# SoC_pwr_2.net
KiCad netlist of a schematic drawn in Altium Designer
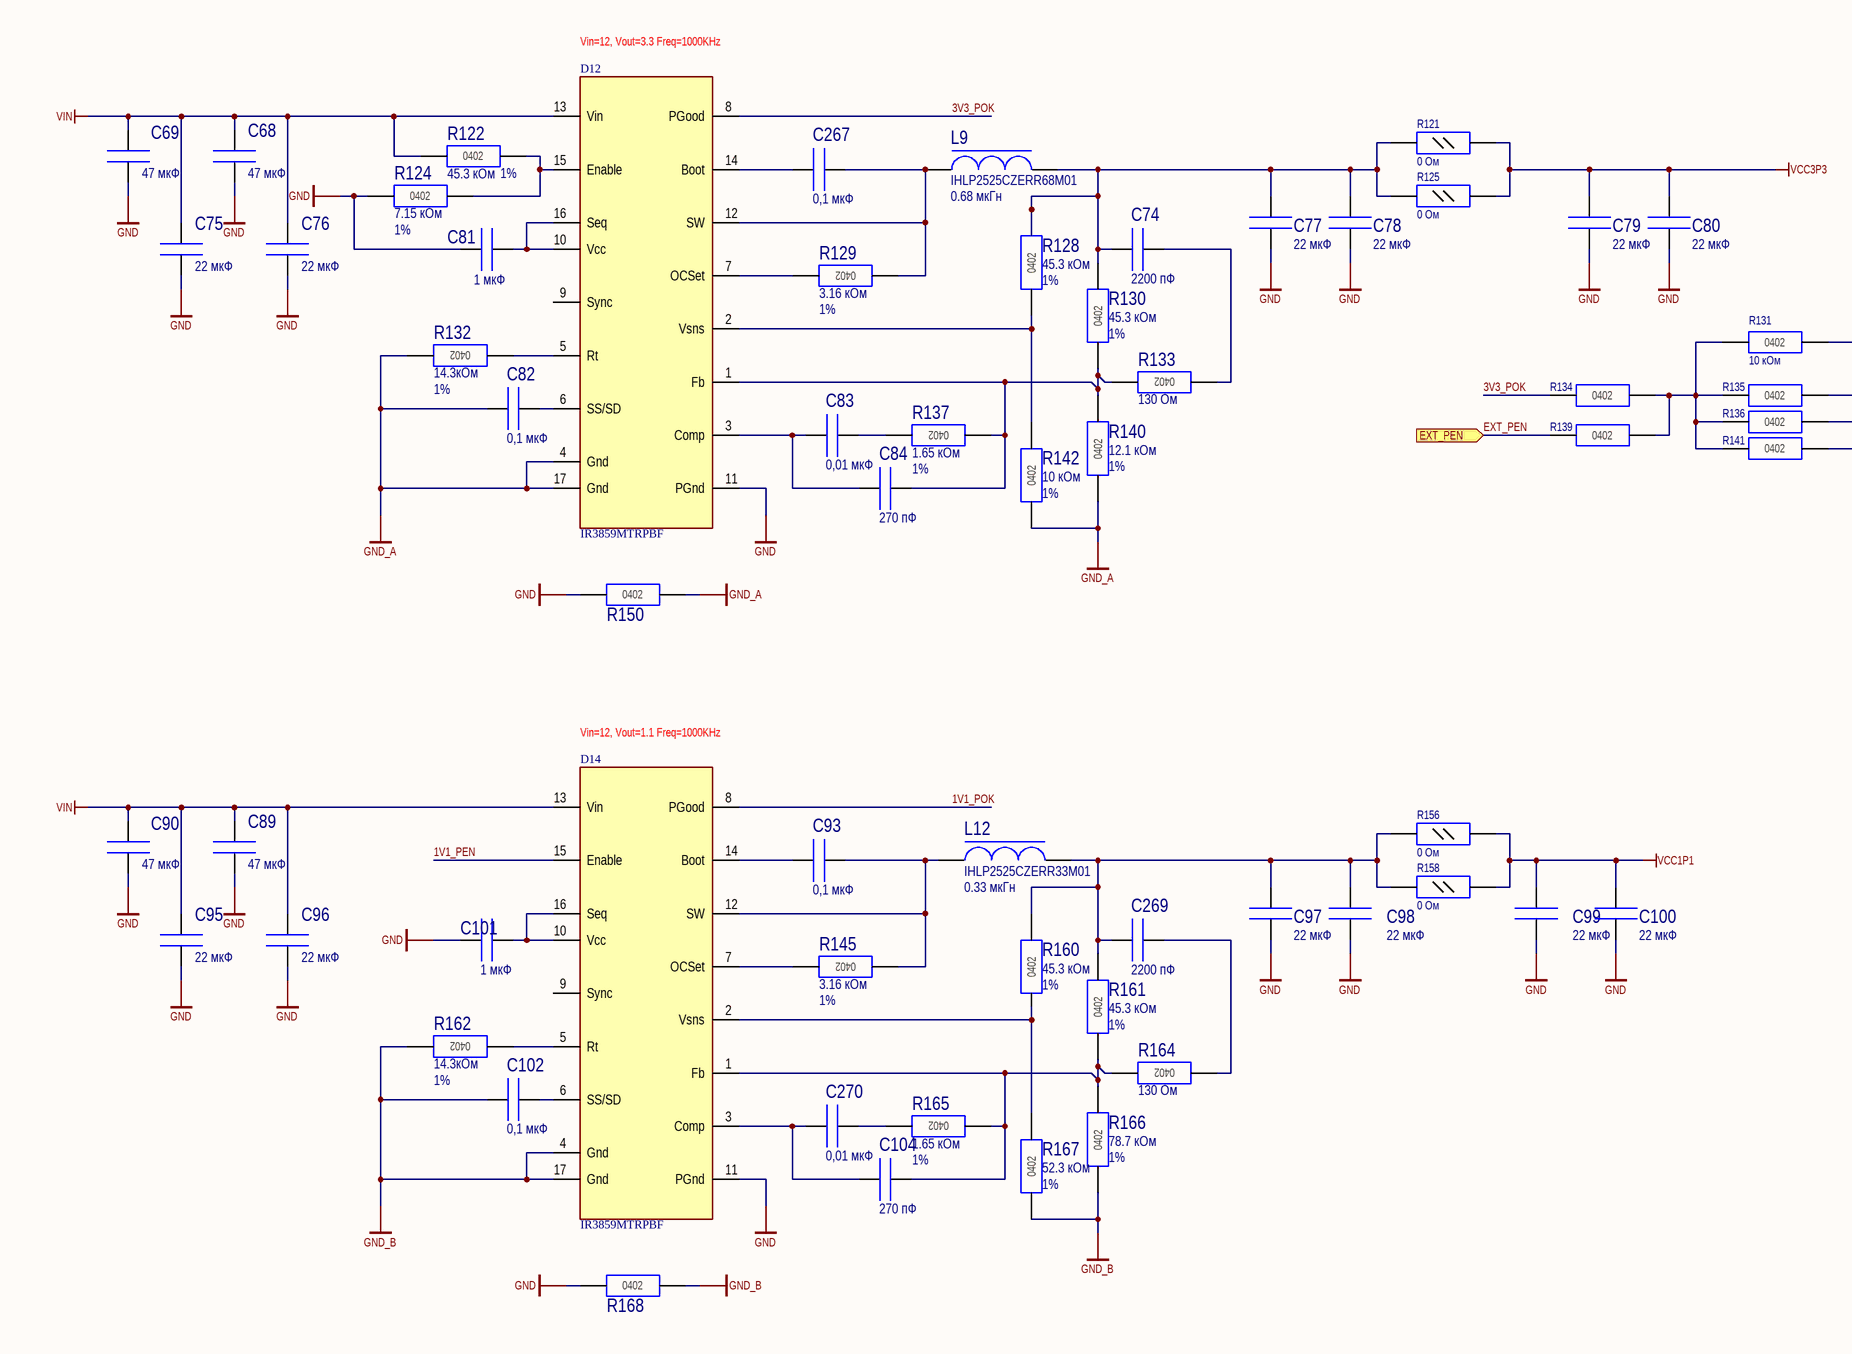
[diagram p0: SoC_pwr_2.SchDoc, left]
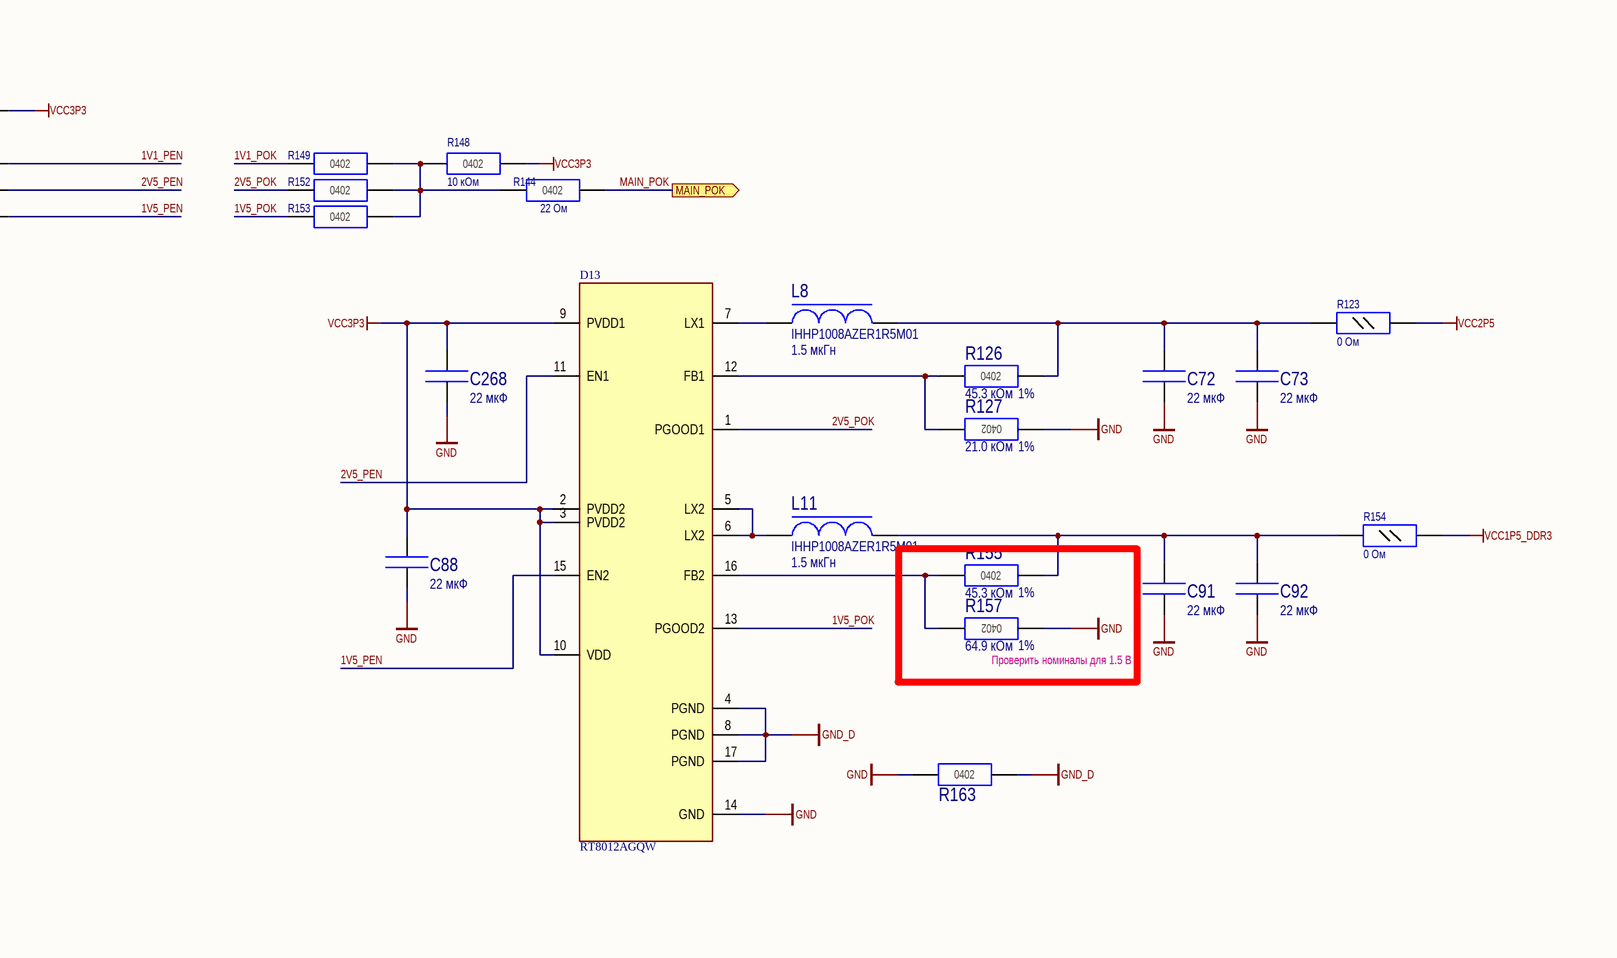
[diagram p1: SoC_pwr_2.SchDoc, right]

(export (version "E")
  (design (tool "Eeschema 10.0.6"))
  (components
    (comp (ref "C68")
      (value "47 мкФ")
      (footprint "CC0603")
      (description "Чип конденсатор керамический")
      (fields (field (name "Comment") "CC0603-X5R-47 мкФ-20%-6,3В"))
      (libsource (lib "Конденсаторы") (part "CC0603-X5R-#-20%-6,3В"))
    )
    (comp (ref "C69")
      (value "47 мкФ")
      (footprint "CC0603")
      (description "Чип конденсатор керамический")
      (fields (field (name "Comment") "CC0603-X5R-47 мкФ-20%-6,3В"))
      (libsource (lib "Конденсаторы") (part "CC0603-X5R-#-20%-6,3В"))
    )
    (comp (ref "C72")
      (value "22 мкФ")
      (footprint "CC0603")
      (description "Чип конденсатор керамический")
      (fields (field (name "Comment") "CC0603-X5R-22 мкФ-20%-6,3В"))
      (libsource (lib "Конденсаторы") (part "CC0603-X5R-#-20%-6,3В"))
    )
    (comp (ref "C73")
      (value "22 мкФ")
      (footprint "CC0603")
      (description "Чип конденсатор керамический")
      (fields (field (name "Comment") "CC0603-X5R-22 мкФ-20%-6,3В"))
      (libsource (lib "Конденсаторы") (part "CC0603-X5R-#-20%-6,3В"))
    )
    (comp (ref "C74")
      (value "2200 пФ")
      (footprint "CC0402(1005)")
      (description "Чип конденсатор керамический")
      (fields (field (name "Comment") "CC0402-X7R-2200 пФ-10%-16В"))
      (libsource (lib "Чип конденсаторы") (part "CC0402-X7R-#-20%-10В"))
    )
    (comp (ref "C75")
      (value "22 мкФ")
      (footprint "CC0603")
      (description "Чип конденсатор керамический")
      (fields (field (name "Comment") "CC0603-X5R-22 мкФ-20%-6,3В"))
      (libsource (lib "Конденсаторы") (part "CC0603-X5R-#-20%-6,3В"))
    )
    (comp (ref "C76")
      (value "22 мкФ")
      (footprint "CC0603")
      (description "Чип конденсатор керамический")
      (fields (field (name "Comment") "CC0603-X5R-22 мкФ-20%-6,3В"))
      (libsource (lib "Конденсаторы") (part "CC0603-X5R-#-20%-6,3В"))
    )
    (comp (ref "C77")
      (value "22 мкФ")
      (footprint "CC0603")
      (description "Чип конденсатор керамический")
      (fields (field (name "Comment") "CC0603-X5R-22 мкФ-20%-6,3В"))
      (libsource (lib "Конденсаторы") (part "CC0603-X5R-#-20%-6,3В"))
    )
    (comp (ref "C78")
      (value "22 мкФ")
      (footprint "CC0603")
      (description "Чип конденсатор керамический")
      (fields (field (name "Comment") "CC0603-X5R-22 мкФ-20%-6,3В"))
      (libsource (lib "Конденсаторы") (part "CC0603-X5R-#-20%-6,3В"))
    )
    (comp (ref "C79")
      (value "22 мкФ")
      (footprint "CC0603")
      (description "Чип конденсатор керамический")
      (fields (field (name "Comment") "CC0603-X5R-22 мкФ-20%-6,3В"))
      (libsource (lib "Конденсаторы") (part "CC0603-X5R-#-20%-6,3В"))
    )
    (comp (ref "C80")
      (value "22 мкФ")
      (footprint "CC0603")
      (description "Чип конденсатор керамический")
      (fields (field (name "Comment") "CC0603-X5R-22 мкФ-20%-6,3В"))
      (libsource (lib "Конденсаторы") (part "CC0603-X5R-#-20%-6,3В"))
    )
    (comp (ref "C81")
      (value "1 мкФ")
      (footprint "CC0603")
      (description "Чип конденсатор керамический")
      (fields (field (name "Comment") "CC0603-X5R-1 мкФ-10%-25В"))
      (libsource (lib "Конденсаторы") (part "CC0603-X5R-#-20%-6,3В"))
    )
    (comp (ref "C82")
      (value "0,1 мкФ")
      (footprint "CC0402(1005)")
      (description "Чип конденсатор керамический")
      (fields (field (name "Comment") "CC0402-X7R-0,1 мкФ-20%-10В"))
      (libsource (lib "Чип конденсаторы") (part "CC0402-X7R-#-20%-10В"))
    )
    (comp (ref "C83")
      (value "0,01 мкФ")
      (footprint "CC0402(1005)")
      (description "Чип конденсатор керамический")
      (fields (field (name "Comment") "CC0402-X7R-0,01 мкФ-10%-50В"))
      (libsource (lib "Чип конденсаторы") (part "CC0402-X7R-#-20%-10В"))
    )
    (comp (ref "C84")
      (value "270 пФ")
      (footprint "CC0402(1005)")
      (description "Чип конденсатор керамический")
      (fields (field (name "Comment") "CC0402-NP0-270 пФ-1%-50В"))
      (libsource (lib "Чип конденсаторы") (part "CC0402-X7R-#-20%-10В"))
    )
    (comp (ref "C88")
      (value "22 мкФ")
      (footprint "CC0603")
      (description "Чип конденсатор керамический")
      (fields (field (name "Comment") "CC0603-X5R-22 мкФ-20%-6,3В"))
      (libsource (lib "Конденсаторы") (part "CC0603-X5R-#-20%-6,3В"))
    )
    (comp (ref "C89")
      (value "47 мкФ")
      (footprint "CC0603")
      (description "Чип конденсатор керамический")
      (fields (field (name "Comment") "CC0603-X5R-47 мкФ-20%-6,3В"))
      (libsource (lib "Конденсаторы") (part "CC0603-X5R-#-20%-6,3В"))
    )
    (comp (ref "C90")
      (value "47 мкФ")
      (footprint "CC0603")
      (description "Чип конденсатор керамический")
      (fields (field (name "Comment") "CC0603-X5R-47 мкФ-20%-6,3В"))
      (libsource (lib "Конденсаторы") (part "CC0603-X5R-#-20%-6,3В"))
    )
    (comp (ref "C91")
      (value "22 мкФ")
      (footprint "CC0603")
      (description "Чип конденсатор керамический")
      (fields (field (name "Comment") "CC0603-X5R-22 мкФ-20%-6,3В"))
      (libsource (lib "Конденсаторы") (part "CC0603-X5R-#-20%-6,3В"))
    )
    (comp (ref "C92")
      (value "22 мкФ")
      (footprint "CC0603")
      (description "Чип конденсатор керамический")
      (fields (field (name "Comment") "CC0603-X5R-22 мкФ-20%-6,3В"))
      (libsource (lib "Конденсаторы") (part "CC0603-X5R-#-20%-6,3В"))
    )
    (comp (ref "C93")
      (value "0,1 мкФ")
      (footprint "CC0402(1005)")
      (description "Чип конденсатор керамический")
      (fields (field (name "Comment") "CC0402-X7R-0,1 мкФ-20%-10В"))
      (libsource (lib "Чип конденсаторы") (part "CC0402-X7R-#-20%-10В"))
    )
    (comp (ref "C95")
      (value "22 мкФ")
      (footprint "CC0603")
      (description "Чип конденсатор керамический")
      (fields (field (name "Comment") "CC0603-X5R-22 мкФ-20%-6,3В"))
      (libsource (lib "Конденсаторы") (part "CC0603-X5R-#-20%-6,3В"))
    )
    (comp (ref "C96")
      (value "22 мкФ")
      (footprint "CC0603")
      (description "Чип конденсатор керамический")
      (fields (field (name "Comment") "CC0603-X5R-22 мкФ-20%-6,3В"))
      (libsource (lib "Конденсаторы") (part "CC0603-X5R-#-20%-6,3В"))
    )
    (comp (ref "C97")
      (value "22 мкФ")
      (footprint "CC0603")
      (description "Чип конденсатор керамический")
      (fields (field (name "Comment") "CC0603-X5R-22 мкФ-20%-6,3В"))
      (libsource (lib "Конденсаторы") (part "CC0603-X5R-#-20%-6,3В"))
    )
    (comp (ref "C98")
      (value "22 мкФ")
      (footprint "CC0603")
      (description "Чип конденсатор керамический")
      (fields (field (name "Comment") "CC0603-X5R-22 мкФ-20%-6,3В"))
      (libsource (lib "Конденсаторы") (part "CC0603-X5R-#-20%-6,3В"))
    )
    (comp (ref "C99")
      (value "22 мкФ")
      (footprint "CC0603")
      (description "Чип конденсатор керамический")
      (fields (field (name "Comment") "CC0603-X5R-22 мкФ-20%-6,3В"))
      (libsource (lib "Конденсаторы") (part "CC0603-X5R-#-20%-6,3В"))
    )
    (comp (ref "C100")
      (value "22 мкФ")
      (footprint "CC0603")
      (description "Чип конденсатор керамический")
      (fields (field (name "Comment") "CC0603-X5R-22 мкФ-20%-6,3В"))
      (libsource (lib "Конденсаторы") (part "CC0603-X5R-#-20%-6,3В"))
    )
    (comp (ref "C101")
      (value "1 мкФ")
      (footprint "CC0603")
      (description "Чип конденсатор керамический")
      (fields (field (name "Comment") "CC0603-X5R-1 мкФ-10%-25В"))
      (libsource (lib "Конденсаторы") (part "CC0603-X5R-#-20%-6,3В"))
    )
    (comp (ref "C102")
      (value "0,1 мкФ")
      (footprint "CC0402(1005)")
      (description "Чип конденсатор керамический")
      (fields (field (name "Comment") "CC0402-X7R-0,1 мкФ-20%-10В"))
      (libsource (lib "Чип конденсаторы") (part "CC0402-X7R-#-20%-10В"))
    )
    (comp (ref "C104")
      (value "270 пФ")
      (footprint "CC0402(1005)")
      (description "Чип конденсатор керамический")
      (fields (field (name "Comment") "CC0402-NP0-270 пФ-1%-50В"))
      (libsource (lib "Чип конденсаторы") (part "CC0402-X7R-#-20%-10В"))
    )
    (comp (ref "C267")
      (value "0,1 мкФ")
      (footprint "CC0402(1005)")
      (description "Чип конденсатор керамический")
      (fields (field (name "Comment") "CC0402-X7R-0,1 мкФ-20%-10В"))
      (libsource (lib "Чип конденсаторы") (part "CC0402-X7R-#-20%-10В"))
    )
    (comp (ref "C268")
      (value "22 мкФ")
      (footprint "CC0603")
      (description "Чип конденсатор керамический")
      (fields (field (name "Comment") "CC0603-X5R-22 мкФ-20%-6,3В"))
      (libsource (lib "Конденсаторы") (part "CC0603-X5R-#-20%-6,3В"))
    )
    (comp (ref "C269")
      (value "2200 пФ")
      (footprint "CC0402(1005)")
      (description "Чип конденсатор керамический")
      (fields (field (name "Comment") "CC0402-X7R-2200 пФ-10%-16В"))
      (libsource (lib "Чип конденсаторы") (part "CC0402-X7R-#-20%-10В"))
    )
    (comp (ref "C270")
      (value "0,01 мкФ")
      (footprint "CC0402(1005)")
      (description "Чип конденсатор керамический")
      (fields (field (name "Comment") "CC0402-X7R-0,01 мкФ-10%-50В"))
      (libsource (lib "Чип конденсаторы") (part "CC0402-X7R-#-20%-10В"))
    )
    (comp (ref "D12")
      (value "IR3859MTRPBF")
      (footprint "IR3859")
      (description "IC REG BUCK ADJ 9A SYNC 17PQFN")
      (libsource (lib "SD_IC") (part "IR3859MPbF"))
    )
    (comp (ref "D13")
      (value "RT8012AGQW")
      (footprint "RT8012AGQW")
      (libsource (lib "SD_IC") (part "RT8012AGQW"))
    )
    (comp (ref "D14")
      (value "IR3859MTRPBF")
      (footprint "IR3859")
      (description "IC REG BUCK ADJ 9A SYNC 17PQFN")
      (libsource (lib "SD_IC") (part "IR3859MPbF"))
    )
    (comp (ref "L8")
      (value "IHHP1008AZER1R5M01")
      (footprint "INDC2720X12L")
      (description "FIXED IND 1.5UH 2.4A 96 MOHM SMD")
      (fields (field (name "ALTIUM_VALUE") "1.5 мкГн"))
      (libsource (lib "SD_IC") (part "L_VISH_IIHHP1008ABE_1"))
    )
    (comp (ref "L9")
      (value "IHLP2525CZERR68M01")
      (footprint "INDP6965X30L")
      (description "FIXED IND 680NH 15.5A 5.5 MOHM")
      (fields (field (name "ALTIUM_VALUE") "0.68 мкГн"))
      (libsource (lib "SD_IC") (part "L_VISH_IHLP2525CZERR68M01"))
    )
    (comp (ref "L11")
      (value "IHHP1008AZER1R5M01")
      (footprint "INDC2720X12L")
      (description "FIXED IND 1.5UH 2.4A 96 MOHM SMD")
      (fields (field (name "ALTIUM_VALUE") "1.5 мкГн"))
      (libsource (lib "SD_IC") (part "L_VISH_IIHHP1008ABE_1"))
    )
    (comp (ref "L12")
      (value "IHLP2525CZERR33M01")
      (footprint "INDP6965X30L")
      (description "FIXED IND 680NH 15.5A 5.5 MOHM")
      (fields (field (name "ALTIUM_VALUE") "0.33 мкГн"))
      (libsource (lib "SD_IC") (part "L_VISH_IHLP2525CZERR68M01"))
    )
    (comp (ref "R121")
      (value "0 Ом")
      (footprint "CR0805")
      (description "Чип резистор")
      (fields (field (name "Comment") "CR0805-0 Ом-±5%"))
      (libsource (lib "Резисторы") (part "CR0805-#-±5%"))
    )
    (comp (ref "R122")
      (value "45.3 кОм")
      (footprint "CR0402(1005)")
      (description "Чип резистор")
      (fields (field (name "TOLERANCE") "1%") (field (name "Comment") "CR0402-45.3 кОм-±1%"))
      (libsource (lib "") (part "CR0402-#-±1%_2"))
    )
    (comp (ref "R123")
      (value "0 Ом")
      (footprint "CR0805")
      (description "Чип резистор")
      (fields (field (name "Comment") "CR0805-0 Ом-±5%"))
      (libsource (lib "Резисторы") (part "CR0805-#-±5%"))
    )
    (comp (ref "R124")
      (value "7.15 кОм")
      (footprint "CR0402(1005)")
      (description "Чип резистор")
      (fields (field (name "TOLERANCE") "1%") (field (name "Comment") "CR0402-7.15 кОм-±1%"))
      (libsource (lib "") (part "CR0402-#-±1%_2"))
    )
    (comp (ref "R125")
      (value "0 Ом")
      (footprint "CR0805")
      (description "Чип резистор")
      (fields (field (name "Comment") "CR0805-0 Ом-±5%"))
      (libsource (lib "Резисторы") (part "CR0805-#-±5%"))
    )
    (comp (ref "R126")
      (value "45.3 кОм")
      (footprint "CR0402(1005)")
      (description "Чип резистор")
      (fields (field (name "TOLERANCE") "1%") (field (name "Comment") "CR0402-45.3 кОм-±1%"))
      (libsource (lib "") (part "CR0402-#-±1%_2"))
    )
    (comp (ref "R127")
      (value "21.0 кОм")
      (footprint "CR0402(1005)")
      (description "Чип резистор")
      (fields (field (name "TOLERANCE") "1%") (field (name "Comment") "CR0402-21.0 кОм-±1%"))
      (libsource (lib "") (part "CR0402-#-±1%_1"))
    )
    (comp (ref "R128")
      (value "45.3 кОм")
      (footprint "CR0402(1005)")
      (description "Чип резистор")
      (fields (field (name "TOLERANCE") "1%") (field (name "Comment") "CR0402-45.3 кОм-±1%"))
      (libsource (lib "Чип резисторы") (part "CR0402-#-±1%"))
    )
    (comp (ref "R129")
      (value "3.16 кОм")
      (footprint "CR0402(1005)")
      (description "Чип резистор")
      (fields (field (name "TOLERANCE") "1%") (field (name "Comment") "CR0402-3.16 кОм-±1%"))
      (libsource (lib "") (part "CR0402-#-±1%_1"))
    )
    (comp (ref "R130")
      (value "45.3 кОм")
      (footprint "CR0402(1005)")
      (description "Чип резистор")
      (fields (field (name "TOLERANCE") "1%") (field (name "Comment") "CR0402-45.3 кОм-±1%"))
      (libsource (lib "Чип резисторы") (part "CR0402-#-±1%"))
    )
    (comp (ref "R131")
      (value "10 кОм")
      (footprint "CR0402(1005)")
      (description "Чип резистор")
      (fields (field (name "TOLERANCE") "5%") (field (name "Comment") "CR0402-10 кОм-±5%"))
      (libsource (lib "Резисторы") (part "CR0402-#-±5%"))
    )
    (comp (ref "R132")
      (value "14.3кОм")
      (footprint "CR0402(1005)")
      (description "Чип резистор")
      (fields (field (name "TOLERANCE") "1%") (field (name "Comment") "CR0402-14.3кОм-±1%"))
      (libsource (lib "") (part "CR0402-#-±1%_1"))
    )
    (comp (ref "R133")
      (value "130 Ом")
      (footprint "CR0402(1005)")
      (description "Чип резистор")
      (fields (field (name "Comment") "CR0402-130 Ом-±1%"))
      (libsource (lib "") (part "CR0402-#-±1%_1"))
    )
    (comp (ref "R134")
      (value "CR0402-0 Ом-±5%")
      (footprint "CR0402(1005)")
      (description "Чип резистор")
      (fields (field (name "TOLERANCE") "5%"))
      (libsource (lib "Резисторы") (part "CR0402-#-±5%"))
    )
    (comp (ref "R135")
      (value "CR0402-0 Ом-±5%")
      (footprint "CR0402(1005)")
      (description "Чип резистор")
      (fields (field (name "TOLERANCE") "5%"))
      (libsource (lib "Резисторы") (part "CR0402-#-±5%"))
    )
    (comp (ref "R136")
      (value "CR0402-0 Ом-±5%")
      (footprint "CR0402(1005)")
      (description "Чип резистор")
      (fields (field (name "TOLERANCE") "5%"))
      (libsource (lib "Резисторы") (part "CR0402-#-±5%"))
    )
    (comp (ref "R137")
      (value "1.65 кОм")
      (footprint "CR0402(1005)")
      (description "Чип резистор")
      (fields (field (name "TOLERANCE") "1%") (field (name "Comment") "CR0402-1.65 кОм-±1%"))
      (libsource (lib "") (part "CR0402-#-±1%_1"))
    )
    (comp (ref "R139")
      (value "CR0402-0 Ом-±5%")
      (footprint "CR0402(1005)")
      (description "Чип резистор")
      (fields (field (name "TOLERANCE") "5%"))
      (libsource (lib "Резисторы") (part "CR0402-#-±5%"))
    )
    (comp (ref "R140")
      (value "12.1 кОм")
      (footprint "CR0402(1005)")
      (description "Чип резистор")
      (fields (field (name "TOLERANCE") "1%") (field (name "Comment") "CR0402-12.1 кОм-±1%"))
      (libsource (lib "Чип резисторы") (part "CR0402-#-±1%"))
    )
    (comp (ref "R141")
      (value "CR0402-0 Ом-±5%")
      (footprint "CR0402(1005)")
      (description "Чип резистор")
      (fields (field (name "TOLERANCE") "5%"))
      (libsource (lib "Резисторы") (part "CR0402-#-±5%"))
    )
    (comp (ref "R142")
      (value "10 кОм")
      (footprint "CR0402(1005)")
      (description "Чип резистор")
      (fields (field (name "TOLERANCE") "1%") (field (name "Comment") "CR0402-10 кОм-±1%"))
      (libsource (lib "Чип резисторы") (part "CR0402-#-±1%"))
    )
    (comp (ref "R144")
      (value "22 Ом")
      (footprint "CR0402(1005)")
      (description "Чип резистор")
      (fields (field (name "TOLERANCE") "5%") (field (name "Comment") "CR0402-22 Ом-±5%"))
      (libsource (lib "Чип резисторы") (part "CR0402-#-±5%"))
    )
    (comp (ref "R145")
      (value "3.16 кОм")
      (footprint "CR0402(1005)")
      (description "Чип резистор")
      (fields (field (name "TOLERANCE") "1%") (field (name "Comment") "CR0402-3.16 кОм-±1%"))
      (libsource (lib "") (part "CR0402-#-±1%_1"))
    )
    (comp (ref "R148")
      (value "10 кОм")
      (footprint "CR0402(1005)")
      (description "Чип резистор")
      (fields (field (name "TOLERANCE") "5%") (field (name "Comment") "CR0402-10 кОм-±5%"))
      (libsource (lib "Резисторы") (part "CR0402-#-±5%"))
    )
    (comp (ref "R149")
      (value "CR0402-0 Ом-±5%")
      (footprint "CR0402(1005)")
      (description "Чип резистор")
      (fields (field (name "TOLERANCE") "5%"))
      (libsource (lib "Резисторы") (part "CR0402-#-±5%"))
    )
    (comp (ref "R150")
      (value "CR0402-0 Ом-±5%")
      (footprint "CR0402(1005)")
      (description "Чип резистор")
      (fields (field (name "TOLERANCE") "5%"))
      (libsource (lib "Резисторы") (part "CR0402-#-±5%"))
    )
    (comp (ref "R152")
      (value "CR0402-0 Ом-±5%")
      (footprint "CR0402(1005)")
      (description "Чип резистор")
      (fields (field (name "TOLERANCE") "5%"))
      (libsource (lib "Резисторы") (part "CR0402-#-±5%"))
    )
    (comp (ref "R153")
      (value "CR0402-0 Ом-±5%")
      (footprint "CR0402(1005)")
      (description "Чип резистор")
      (fields (field (name "TOLERANCE") "5%"))
      (libsource (lib "Резисторы") (part "CR0402-#-±5%"))
    )
    (comp (ref "R154")
      (value "0 Ом")
      (footprint "CR0805")
      (description "Чип резистор")
      (fields (field (name "Comment") "CR0805-0 Ом-±5%"))
      (libsource (lib "Резисторы") (part "CR0805-#-±5%"))
    )
    (comp (ref "R155")
      (value "45.3 кОм")
      (footprint "CR0402(1005)")
      (description "Чип резистор")
      (fields (field (name "TOLERANCE") "1%") (field (name "Comment") "CR0402-45.3 кОм-±1%"))
      (libsource (lib "") (part "CR0402-#-±1%_2"))
    )
    (comp (ref "R156")
      (value "0 Ом")
      (footprint "CR0805")
      (description "Чип резистор")
      (fields (field (name "Comment") "CR0805-0 Ом-±5%"))
      (libsource (lib "Резисторы") (part "CR0805-#-±5%"))
    )
    (comp (ref "R157")
      (value "64.9 кОм")
      (footprint "CR0402(1005)")
      (description "Чип резистор")
      (fields (field (name "TOLERANCE") "1%") (field (name "Comment") "CR0402-64.9 кОм-±1%"))
      (libsource (lib "") (part "CR0402-#-±1%_1"))
    )
    (comp (ref "R158")
      (value "0 Ом")
      (footprint "CR0805")
      (description "Чип резистор")
      (fields (field (name "Comment") "CR0805-0 Ом-±5%"))
      (libsource (lib "Резисторы") (part "CR0805-#-±5%"))
    )
    (comp (ref "R160")
      (value "45.3 кОм")
      (footprint "CR0402(1005)")
      (description "Чип резистор")
      (fields (field (name "TOLERANCE") "1%") (field (name "Comment") "CR0402-45.3 кОм-±1%"))
      (libsource (lib "Чип резисторы") (part "CR0402-#-±1%"))
    )
    (comp (ref "R161")
      (value "45.3 кОм")
      (footprint "CR0402(1005)")
      (description "Чип резистор")
      (fields (field (name "TOLERANCE") "1%") (field (name "Comment") "CR0402-45.3 кОм-±1%"))
      (libsource (lib "Чип резисторы") (part "CR0402-#-±1%"))
    )
    (comp (ref "R162")
      (value "14.3кОм")
      (footprint "CR0402(1005)")
      (description "Чип резистор")
      (fields (field (name "TOLERANCE") "1%") (field (name "Comment") "CR0402-14.3кОм-±1%"))
      (libsource (lib "") (part "CR0402-#-±1%_1"))
    )
    (comp (ref "R163")
      (value "CR0402-0 Ом-±5%")
      (footprint "CR0402(1005)")
      (description "Чип резистор")
      (fields (field (name "TOLERANCE") "5%"))
      (libsource (lib "Резисторы") (part "CR0402-#-±5%"))
    )
    (comp (ref "R164")
      (value "130 Ом")
      (footprint "CR0402(1005)")
      (description "Чип резистор")
      (fields (field (name "Comment") "CR0402-130 Ом-±1%"))
      (libsource (lib "") (part "CR0402-#-±1%_1"))
    )
    (comp (ref "R165")
      (value "1.65 кОм")
      (footprint "CR0402(1005)")
      (description "Чип резистор")
      (fields (field (name "TOLERANCE") "1%") (field (name "Comment") "CR0402-1.65 кОм-±1%"))
      (libsource (lib "") (part "CR0402-#-±1%_1"))
    )
    (comp (ref "R166")
      (value "78.7 кОм")
      (footprint "CR0402(1005)")
      (description "Чип резистор")
      (fields (field (name "TOLERANCE") "1%") (field (name "Comment") "CR0402-78.7 кОм-±1%"))
      (libsource (lib "Чип резисторы") (part "CR0402-#-±1%"))
    )
    (comp (ref "R167")
      (value "52.3 кОм")
      (footprint "CR0402(1005)")
      (description "Чип резистор")
      (fields (field (name "TOLERANCE") "1%") (field (name "Comment") "CR0402-52.3 кОм-±1%"))
      (libsource (lib "Чип резисторы") (part "CR0402-#-±1%"))
    )
    (comp (ref "R168")
      (value "CR0402-0 Ом-±5%")
      (footprint "CR0402(1005)")
      (description "Чип резистор")
      (fields (field (name "TOLERANCE") "5%"))
      (libsource (lib "Резисторы") (part "CR0402-#-±5%"))
    )
  )
  (nets
    (net (code "1") (name "/1V1_PEN") (class "Default")
      (node (ref "D14") (pin "15") (pinfunction "Enable_15") (pintype "passive"))
      (node (ref "R135") (pin "2") (pinfunction "-_2") (pintype "passive"))
    )
    (net (code "2") (name "/1V1_POK") (class "Default")
      (node (ref "D14") (pin "8") (pinfunction "PGood_8") (pintype "passive"))
      (node (ref "R149") (pin "1") (pinfunction "+_1") (pintype "passive"))
    )
    (net (code "3") (name "/1V5_PEN") (class "Default")
      (node (ref "D13") (pin "15") (pinfunction "EN2_15") (pintype "passive"))
      (node (ref "R141") (pin "2") (pinfunction "-_2") (pintype "passive"))
    )
    (net (code "4") (name "/1V5_POK") (class "Default")
      (node (ref "D13") (pin "13") (pinfunction "PGOOD2_13") (pintype "passive"))
      (node (ref "R153") (pin "1") (pinfunction "+_1") (pintype "passive"))
    )
    (net (code "5") (name "/2V5_PEN") (class "Default")
      (node (ref "D13") (pin "11") (pinfunction "EN1_11") (pintype "passive"))
      (node (ref "R136") (pin "2") (pinfunction "-_2") (pintype "passive"))
    )
    (net (code "6") (name "/2V5_POK") (class "Default")
      (node (ref "D13") (pin "1") (pinfunction "PGOOD1_1") (pintype "passive"))
      (node (ref "R152") (pin "1") (pinfunction "+_1") (pintype "passive"))
    )
    (net (code "7") (name "/3V3_POK") (class "Default")
      (node (ref "D12") (pin "8") (pinfunction "PGood_8") (pintype "passive"))
      (node (ref "R134") (pin "1") (pinfunction "+_1") (pintype "passive"))
    )
    (net (code "8") (name "/EXT_PEN") (class "Default")
      (node (ref "R139") (pin "1") (pinfunction "+_1") (pintype "passive"))
    )
    (net (code "9") (name "/MAIN_POK") (class "Default")
      (node (ref "R144") (pin "2") (pinfunction "-_2") (pintype "passive"))
    )
    (net (code "10") (name "GND") (class "Default")
      (node (ref "C100") (pin "2") (pinfunction "-_2") (pintype "passive"))
      (node (ref "C101") (pin "1") (pinfunction "+_1") (pintype "passive"))
      (node (ref "C268") (pin "2") (pinfunction "-_2") (pintype "passive"))
      (node (ref "C68") (pin "2") (pinfunction "-_2") (pintype "passive"))
      (node (ref "C69") (pin "2") (pinfunction "-_2") (pintype "passive"))
      (node (ref "C72") (pin "2") (pinfunction "-_2") (pintype "passive"))
      (node (ref "C73") (pin "2") (pinfunction "-_2") (pintype "passive"))
      (node (ref "C75") (pin "2") (pinfunction "-_2") (pintype "passive"))
      (node (ref "C76") (pin "2") (pinfunction "-_2") (pintype "passive"))
      (node (ref "C77") (pin "2") (pinfunction "-_2") (pintype "passive"))
      (node (ref "C78") (pin "2") (pinfunction "-_2") (pintype "passive"))
      (node (ref "C79") (pin "2") (pinfunction "-_2") (pintype "passive"))
      (node (ref "C80") (pin "2") (pinfunction "-_2") (pintype "passive"))
      (node (ref "C81") (pin "1") (pinfunction "+_1") (pintype "passive"))
      (node (ref "C88") (pin "2") (pinfunction "-_2") (pintype "passive"))
      (node (ref "C89") (pin "2") (pinfunction "-_2") (pintype "passive"))
      (node (ref "C90") (pin "2") (pinfunction "-_2") (pintype "passive"))
      (node (ref "C91") (pin "2") (pinfunction "-_2") (pintype "passive"))
      (node (ref "C92") (pin "2") (pinfunction "-_2") (pintype "passive"))
      (node (ref "C95") (pin "2") (pinfunction "-_2") (pintype "passive"))
      (node (ref "C96") (pin "2") (pinfunction "-_2") (pintype "passive"))
      (node (ref "C97") (pin "2") (pinfunction "-_2") (pintype "passive"))
      (node (ref "C98") (pin "2") (pinfunction "-_2") (pintype "passive"))
      (node (ref "C99") (pin "2") (pinfunction "-_2") (pintype "passive"))
      (node (ref "D12") (pin "11") (pinfunction "PGnd_11") (pintype "passive"))
      (node (ref "D13") (pin "14") (pinfunction "GND_14") (pintype "passive"))
      (node (ref "D14") (pin "11") (pinfunction "PGnd_11") (pintype "passive"))
      (node (ref "R124") (pin "1") (pinfunction "+_1") (pintype "passive"))
      (node (ref "R127") (pin "1") (pinfunction "+_1") (pintype "passive"))
      (node (ref "R150") (pin "1") (pinfunction "+_1") (pintype "passive"))
      (node (ref "R157") (pin "1") (pinfunction "+_1") (pintype "passive"))
      (node (ref "R163") (pin "1") (pinfunction "+_1") (pintype "passive"))
      (node (ref "R168") (pin "1") (pinfunction "+_1") (pintype "passive"))
    )
    (net (code "11") (name "GND_A") (class "Default")
      (node (ref "C82") (pin "1") (pinfunction "+_1") (pintype "passive"))
      (node (ref "D12") (pin "17") (pinfunction "Gnd_17") (pintype "passive"))
      (node (ref "D12") (pin "4") (pinfunction "Gnd_4") (pintype "passive"))
      (node (ref "R132") (pin "2") (pinfunction "-_2") (pintype "passive"))
      (node (ref "R140") (pin "1") (pinfunction "+_1") (pintype "passive"))
      (node (ref "R142") (pin "1") (pinfunction "+_1") (pintype "passive"))
      (node (ref "R150") (pin "2") (pinfunction "-_2") (pintype "passive"))
    )
    (net (code "12") (name "GND_B") (class "Default")
      (node (ref "C102") (pin "1") (pinfunction "+_1") (pintype "passive"))
      (node (ref "D14") (pin "17") (pinfunction "Gnd_17") (pintype "passive"))
      (node (ref "D14") (pin "4") (pinfunction "Gnd_4") (pintype "passive"))
      (node (ref "R162") (pin "2") (pinfunction "-_2") (pintype "passive"))
      (node (ref "R166") (pin "1") (pinfunction "+_1") (pintype "passive"))
      (node (ref "R167") (pin "1") (pinfunction "+_1") (pintype "passive"))
      (node (ref "R168") (pin "2") (pinfunction "-_2") (pintype "passive"))
    )
    (net (code "13") (name "GND_D") (class "Default")
      (node (ref "D13") (pin "17") (pinfunction "PGND_17") (pintype "passive"))
      (node (ref "D13") (pin "4") (pinfunction "PGND_4") (pintype "passive"))
      (node (ref "D13") (pin "8") (pinfunction "PGND_8") (pintype "passive"))
      (node (ref "R163") (pin "2") (pinfunction "-_2") (pintype "passive"))
    )
    (net (code "14") (name "Net-(C72-+)") (class "Default")
      (node (ref "C72") (pin "1") (pinfunction "+_1") (pintype "passive"))
      (node (ref "C73") (pin "1") (pinfunction "+_1") (pintype "passive"))
      (node (ref "L8") (pin "2") (pinfunction "2_2") (pintype "passive"))
      (node (ref "R123") (pin "1") (pinfunction "+_1") (pintype "passive"))
      (node (ref "R126") (pin "2") (pinfunction "-_2") (pintype "passive"))
    )
    (net (code "15") (name "Net-(C74-+)") (class "Default")
      (node (ref "C74") (pin "1") (pinfunction "+_1") (pintype "passive"))
      (node (ref "R133") (pin "1") (pinfunction "+_1") (pintype "passive"))
    )
    (net (code "16") (name "Net-(C74--)") (class "Default")
      (node (ref "C74") (pin "2") (pinfunction "-_2") (pintype "passive"))
      (node (ref "C77") (pin "1") (pinfunction "+_1") (pintype "passive"))
      (node (ref "C78") (pin "1") (pinfunction "+_1") (pintype "passive"))
      (node (ref "L9") (pin "2") (pinfunction "2_2") (pintype "passive"))
      (node (ref "R121") (pin "1") (pinfunction "+_1") (pintype "passive"))
      (node (ref "R125") (pin "1") (pinfunction "+_1") (pintype "passive"))
      (node (ref "R128") (pin "2") (pinfunction "-_2") (pintype "passive"))
      (node (ref "R130") (pin "2") (pinfunction "-_2") (pintype "passive"))
    )
    (net (code "17") (name "Net-(C81--)") (class "Default")
      (node (ref "C81") (pin "2") (pinfunction "-_2") (pintype "passive"))
      (node (ref "D12") (pin "10") (pinfunction "Vcc_10") (pintype "passive"))
      (node (ref "D12") (pin "16") (pinfunction "Seq_16") (pintype "passive"))
    )
    (net (code "18") (name "Net-(C82--)") (class "Default")
      (node (ref "C82") (pin "2") (pinfunction "-_2") (pintype "passive"))
      (node (ref "D12") (pin "6") (pinfunction "SS/SD_6") (pintype "passive"))
    )
    (net (code "19") (name "Net-(C83-+)") (class "Default")
      (node (ref "C83") (pin "1") (pinfunction "+_1") (pintype "passive"))
      (node (ref "C84") (pin "2") (pinfunction "-_2") (pintype "passive"))
      (node (ref "D12") (pin "3") (pinfunction "Comp_3") (pintype "passive"))
    )
    (net (code "20") (name "Net-(C83--)") (class "Default")
      (node (ref "C83") (pin "2") (pinfunction "-_2") (pintype "passive"))
      (node (ref "R137") (pin "2") (pinfunction "-_2") (pintype "passive"))
    )
    (net (code "21") (name "Net-(C84-+)") (class "Default")
      (node (ref "C84") (pin "1") (pinfunction "+_1") (pintype "passive"))
      (node (ref "D12") (pin "1") (pinfunction "Fb_1") (pintype "passive"))
      (node (ref "R130") (pin "1") (pinfunction "+_1") (pintype "passive"))
      (node (ref "R133") (pin "2") (pinfunction "-_2") (pintype "passive"))
      (node (ref "R137") (pin "1") (pinfunction "+_1") (pintype "passive"))
      (node (ref "R140") (pin "2") (pinfunction "-_2") (pintype "passive"))
    )
    (net (code "22") (name "Net-(C91-+)") (class "Default")
      (node (ref "C91") (pin "1") (pinfunction "+_1") (pintype "passive"))
      (node (ref "C92") (pin "1") (pinfunction "+_1") (pintype "passive"))
      (node (ref "L11") (pin "2") (pinfunction "2_2") (pintype "passive"))
      (node (ref "R154") (pin "1") (pinfunction "+_1") (pintype "passive"))
      (node (ref "R155") (pin "2") (pinfunction "-_2") (pintype "passive"))
    )
    (net (code "23") (name "Net-(C93-+)") (class "Default")
      (node (ref "C93") (pin "1") (pinfunction "+_1") (pintype "passive"))
      (node (ref "D14") (pin "14") (pinfunction "Boot_14") (pintype "passive"))
    )
    (net (code "24") (name "Net-(C93--)") (class "Default")
      (node (ref "C93") (pin "2") (pinfunction "-_2") (pintype "passive"))
      (node (ref "D14") (pin "12") (pinfunction "SW_12") (pintype "passive"))
      (node (ref "L12") (pin "1") (pinfunction "1_1") (pintype "passive"))
      (node (ref "R145") (pin "1") (pinfunction "+_1") (pintype "passive"))
    )
    (net (code "25") (name "Net-(C101--)") (class "Default")
      (node (ref "C101") (pin "2") (pinfunction "-_2") (pintype "passive"))
      (node (ref "D14") (pin "10") (pinfunction "Vcc_10") (pintype "passive"))
      (node (ref "D14") (pin "16") (pinfunction "Seq_16") (pintype "passive"))
    )
    (net (code "26") (name "Net-(C102--)") (class "Default")
      (node (ref "C102") (pin "2") (pinfunction "-_2") (pintype "passive"))
      (node (ref "D14") (pin "6") (pinfunction "SS/SD_6") (pintype "passive"))
    )
    (net (code "27") (name "Net-(C104-+)") (class "Default")
      (node (ref "C104") (pin "1") (pinfunction "+_1") (pintype "passive"))
      (node (ref "D14") (pin "1") (pinfunction "Fb_1") (pintype "passive"))
      (node (ref "R161") (pin "1") (pinfunction "+_1") (pintype "passive"))
      (node (ref "R164") (pin "2") (pinfunction "-_2") (pintype "passive"))
      (node (ref "R165") (pin "1") (pinfunction "+_1") (pintype "passive"))
      (node (ref "R166") (pin "2") (pinfunction "-_2") (pintype "passive"))
    )
    (net (code "28") (name "Net-(C104--)") (class "Default")
      (node (ref "C104") (pin "2") (pinfunction "-_2") (pintype "passive"))
      (node (ref "C270") (pin "1") (pinfunction "+_1") (pintype "passive"))
      (node (ref "D14") (pin "3") (pinfunction "Comp_3") (pintype "passive"))
    )
    (net (code "29") (name "Net-(C267-+)") (class "Default")
      (node (ref "C267") (pin "1") (pinfunction "+_1") (pintype "passive"))
      (node (ref "D12") (pin "14") (pinfunction "Boot_14") (pintype "passive"))
    )
    (net (code "30") (name "Net-(C267--)") (class "Default")
      (node (ref "C267") (pin "2") (pinfunction "-_2") (pintype "passive"))
      (node (ref "D12") (pin "12") (pinfunction "SW_12") (pintype "passive"))
      (node (ref "L9") (pin "1") (pinfunction "1_1") (pintype "passive"))
      (node (ref "R129") (pin "1") (pinfunction "+_1") (pintype "passive"))
    )
    (net (code "31") (name "Net-(C269-+)") (class "Default")
      (node (ref "C269") (pin "1") (pinfunction "+_1") (pintype "passive"))
      (node (ref "R164") (pin "1") (pinfunction "+_1") (pintype "passive"))
    )
    (net (code "32") (name "Net-(C269--)") (class "Default")
      (node (ref "C269") (pin "2") (pinfunction "-_2") (pintype "passive"))
      (node (ref "C97") (pin "1") (pinfunction "+_1") (pintype "passive"))
      (node (ref "C98") (pin "1") (pinfunction "+_1") (pintype "passive"))
      (node (ref "L12") (pin "2") (pinfunction "2_2") (pintype "passive"))
      (node (ref "R156") (pin "1") (pinfunction "+_1") (pintype "passive"))
      (node (ref "R158") (pin "1") (pinfunction "+_1") (pintype "passive"))
      (node (ref "R160") (pin "2") (pinfunction "-_2") (pintype "passive"))
      (node (ref "R161") (pin "2") (pinfunction "-_2") (pintype "passive"))
    )
    (net (code "33") (name "Net-(C270--)") (class "Default")
      (node (ref "C270") (pin "2") (pinfunction "-_2") (pintype "passive"))
      (node (ref "R165") (pin "2") (pinfunction "-_2") (pintype "passive"))
    )
    (net (code "34") (name "Net-(D12-Enable)") (class "Default")
      (node (ref "D12") (pin "15") (pinfunction "Enable_15") (pintype "passive"))
      (node (ref "R122") (pin "2") (pinfunction "-_2") (pintype "passive"))
      (node (ref "R124") (pin "2") (pinfunction "-_2") (pintype "passive"))
    )
    (net (code "35") (name "Net-(D12-OCSet)") (class "Default")
      (node (ref "D12") (pin "7") (pinfunction "OCSet_7") (pintype "passive"))
      (node (ref "R129") (pin "2") (pinfunction "-_2") (pintype "passive"))
    )
    (net (code "36") (name "Net-(D12-Rt)") (class "Default")
      (node (ref "D12") (pin "5") (pinfunction "Rt_5") (pintype "passive"))
      (node (ref "R132") (pin "1") (pinfunction "+_1") (pintype "passive"))
    )
    (net (code "37") (name "Net-(D12-Vsns)") (class "Default")
      (node (ref "D12") (pin "2") (pinfunction "Vsns_2") (pintype "passive"))
      (node (ref "R128") (pin "1") (pinfunction "+_1") (pintype "passive"))
      (node (ref "R142") (pin "2") (pinfunction "-_2") (pintype "passive"))
    )
    (net (code "38") (name "Net-(D13-FB1)") (class "Default")
      (node (ref "D13") (pin "12") (pinfunction "FB1_12") (pintype "passive"))
      (node (ref "R126") (pin "1") (pinfunction "+_1") (pintype "passive"))
      (node (ref "R127") (pin "2") (pinfunction "-_2") (pintype "passive"))
    )
    (net (code "39") (name "Net-(D13-FB2)") (class "Default")
      (node (ref "D13") (pin "16") (pinfunction "FB2_16") (pintype "passive"))
      (node (ref "R155") (pin "1") (pinfunction "+_1") (pintype "passive"))
      (node (ref "R157") (pin "2") (pinfunction "-_2") (pintype "passive"))
    )
    (net (code "40") (name "Net-(D13-LX1)") (class "Default")
      (node (ref "D13") (pin "7") (pinfunction "LX1_7") (pintype "passive"))
      (node (ref "L8") (pin "1") (pinfunction "1_1") (pintype "passive"))
    )
    (net (code "41") (name "Net-(D13-LX2-Pad5)") (class "Default")
      (node (ref "D13") (pin "5") (pinfunction "LX2_5") (pintype "passive"))
      (node (ref "D13") (pin "6") (pinfunction "LX2_6") (pintype "passive"))
      (node (ref "L11") (pin "1") (pinfunction "1_1") (pintype "passive"))
    )
    (net (code "42") (name "Net-(D14-OCSet)") (class "Default")
      (node (ref "D14") (pin "7") (pinfunction "OCSet_7") (pintype "passive"))
      (node (ref "R145") (pin "2") (pinfunction "-_2") (pintype "passive"))
    )
    (net (code "43") (name "Net-(D14-Rt)") (class "Default")
      (node (ref "D14") (pin "5") (pinfunction "Rt_5") (pintype "passive"))
      (node (ref "R162") (pin "1") (pinfunction "+_1") (pintype "passive"))
    )
    (net (code "44") (name "Net-(D14-Vsns)") (class "Default")
      (node (ref "D14") (pin "2") (pinfunction "Vsns_2") (pintype "passive"))
      (node (ref "R160") (pin "1") (pinfunction "+_1") (pintype "passive"))
      (node (ref "R167") (pin "2") (pinfunction "-_2") (pintype "passive"))
    )
    (net (code "45") (name "Net-(R131-+)") (class "Default")
      (node (ref "R131") (pin "1") (pinfunction "+_1") (pintype "passive"))
      (node (ref "R134") (pin "2") (pinfunction "-_2") (pintype "passive"))
      (node (ref "R135") (pin "1") (pinfunction "+_1") (pintype "passive"))
      (node (ref "R136") (pin "1") (pinfunction "+_1") (pintype "passive"))
      (node (ref "R139") (pin "2") (pinfunction "-_2") (pintype "passive"))
      (node (ref "R141") (pin "1") (pinfunction "+_1") (pintype "passive"))
    )
    (net (code "46") (name "Net-(R144-+)") (class "Default")
      (node (ref "R144") (pin "1") (pinfunction "+_1") (pintype "passive"))
      (node (ref "R148") (pin "1") (pinfunction "+_1") (pintype "passive"))
      (node (ref "R149") (pin "2") (pinfunction "-_2") (pintype "passive"))
      (node (ref "R152") (pin "2") (pinfunction "-_2") (pintype "passive"))
      (node (ref "R153") (pin "2") (pinfunction "-_2") (pintype "passive"))
    )
    (net (code "47") (name "VCC1P1") (class "Default")
      (node (ref "C100") (pin "1") (pinfunction "+_1") (pintype "passive"))
      (node (ref "C99") (pin "1") (pinfunction "+_1") (pintype "passive"))
      (node (ref "R156") (pin "2") (pinfunction "-_2") (pintype "passive"))
      (node (ref "R158") (pin "2") (pinfunction "-_2") (pintype "passive"))
    )
    (net (code "48") (name "VCC1P5_DDR3") (class "Default")
      (node (ref "R154") (pin "2") (pinfunction "-_2") (pintype "passive"))
    )
    (net (code "49") (name "VCC2P5") (class "Default")
      (node (ref "R123") (pin "2") (pinfunction "-_2") (pintype "passive"))
    )
    (net (code "50") (name "VCC3P3") (class "Default")
      (node (ref "C268") (pin "1") (pinfunction "+_1") (pintype "passive"))
      (node (ref "C79") (pin "1") (pinfunction "+_1") (pintype "passive"))
      (node (ref "C80") (pin "1") (pinfunction "+_1") (pintype "passive"))
      (node (ref "C88") (pin "1") (pinfunction "+_1") (pintype "passive"))
      (node (ref "D13") (pin "10") (pinfunction "VDD_10") (pintype "passive"))
      (node (ref "D13") (pin "2") (pinfunction "PVDD2_2") (pintype "passive"))
      (node (ref "D13") (pin "3") (pinfunction "PVDD2_3") (pintype "passive"))
      (node (ref "D13") (pin "9") (pinfunction "PVDD1_9") (pintype "passive"))
      (node (ref "R121") (pin "2") (pinfunction "-_2") (pintype "passive"))
      (node (ref "R125") (pin "2") (pinfunction "-_2") (pintype "passive"))
      (node (ref "R131") (pin "2") (pinfunction "-_2") (pintype "passive"))
      (node (ref "R148") (pin "2") (pinfunction "-_2") (pintype "passive"))
    )
    (net (code "51") (name "VIN") (class "Default")
      (node (ref "C68") (pin "1") (pinfunction "+_1") (pintype "passive"))
      (node (ref "C69") (pin "1") (pinfunction "+_1") (pintype "passive"))
      (node (ref "C75") (pin "1") (pinfunction "+_1") (pintype "passive"))
      (node (ref "C76") (pin "1") (pinfunction "+_1") (pintype "passive"))
      (node (ref "C89") (pin "1") (pinfunction "+_1") (pintype "passive"))
      (node (ref "C90") (pin "1") (pinfunction "+_1") (pintype "passive"))
      (node (ref "C95") (pin "1") (pinfunction "+_1") (pintype "passive"))
      (node (ref "C96") (pin "1") (pinfunction "+_1") (pintype "passive"))
      (node (ref "D12") (pin "13") (pinfunction "Vin_13") (pintype "passive"))
      (node (ref "D14") (pin "13") (pinfunction "Vin_13") (pintype "passive"))
      (node (ref "R122") (pin "1") (pinfunction "+_1") (pintype "passive"))
    )
    (net (code "52") (name "unconnected-(D12-Sync-Pad9)") (class "Default")
      (node (ref "D12") (pin "9") (pinfunction "Sync_9") (pintype "passive"))
    )
    (net (code "53") (name "unconnected-(D14-Sync-Pad9)") (class "Default")
      (node (ref "D14") (pin "9") (pinfunction "Sync_9") (pintype "passive"))
    )
  )
)
